# terrarium_board.net
KiCad netlist of a schematic drawn in EAGLE
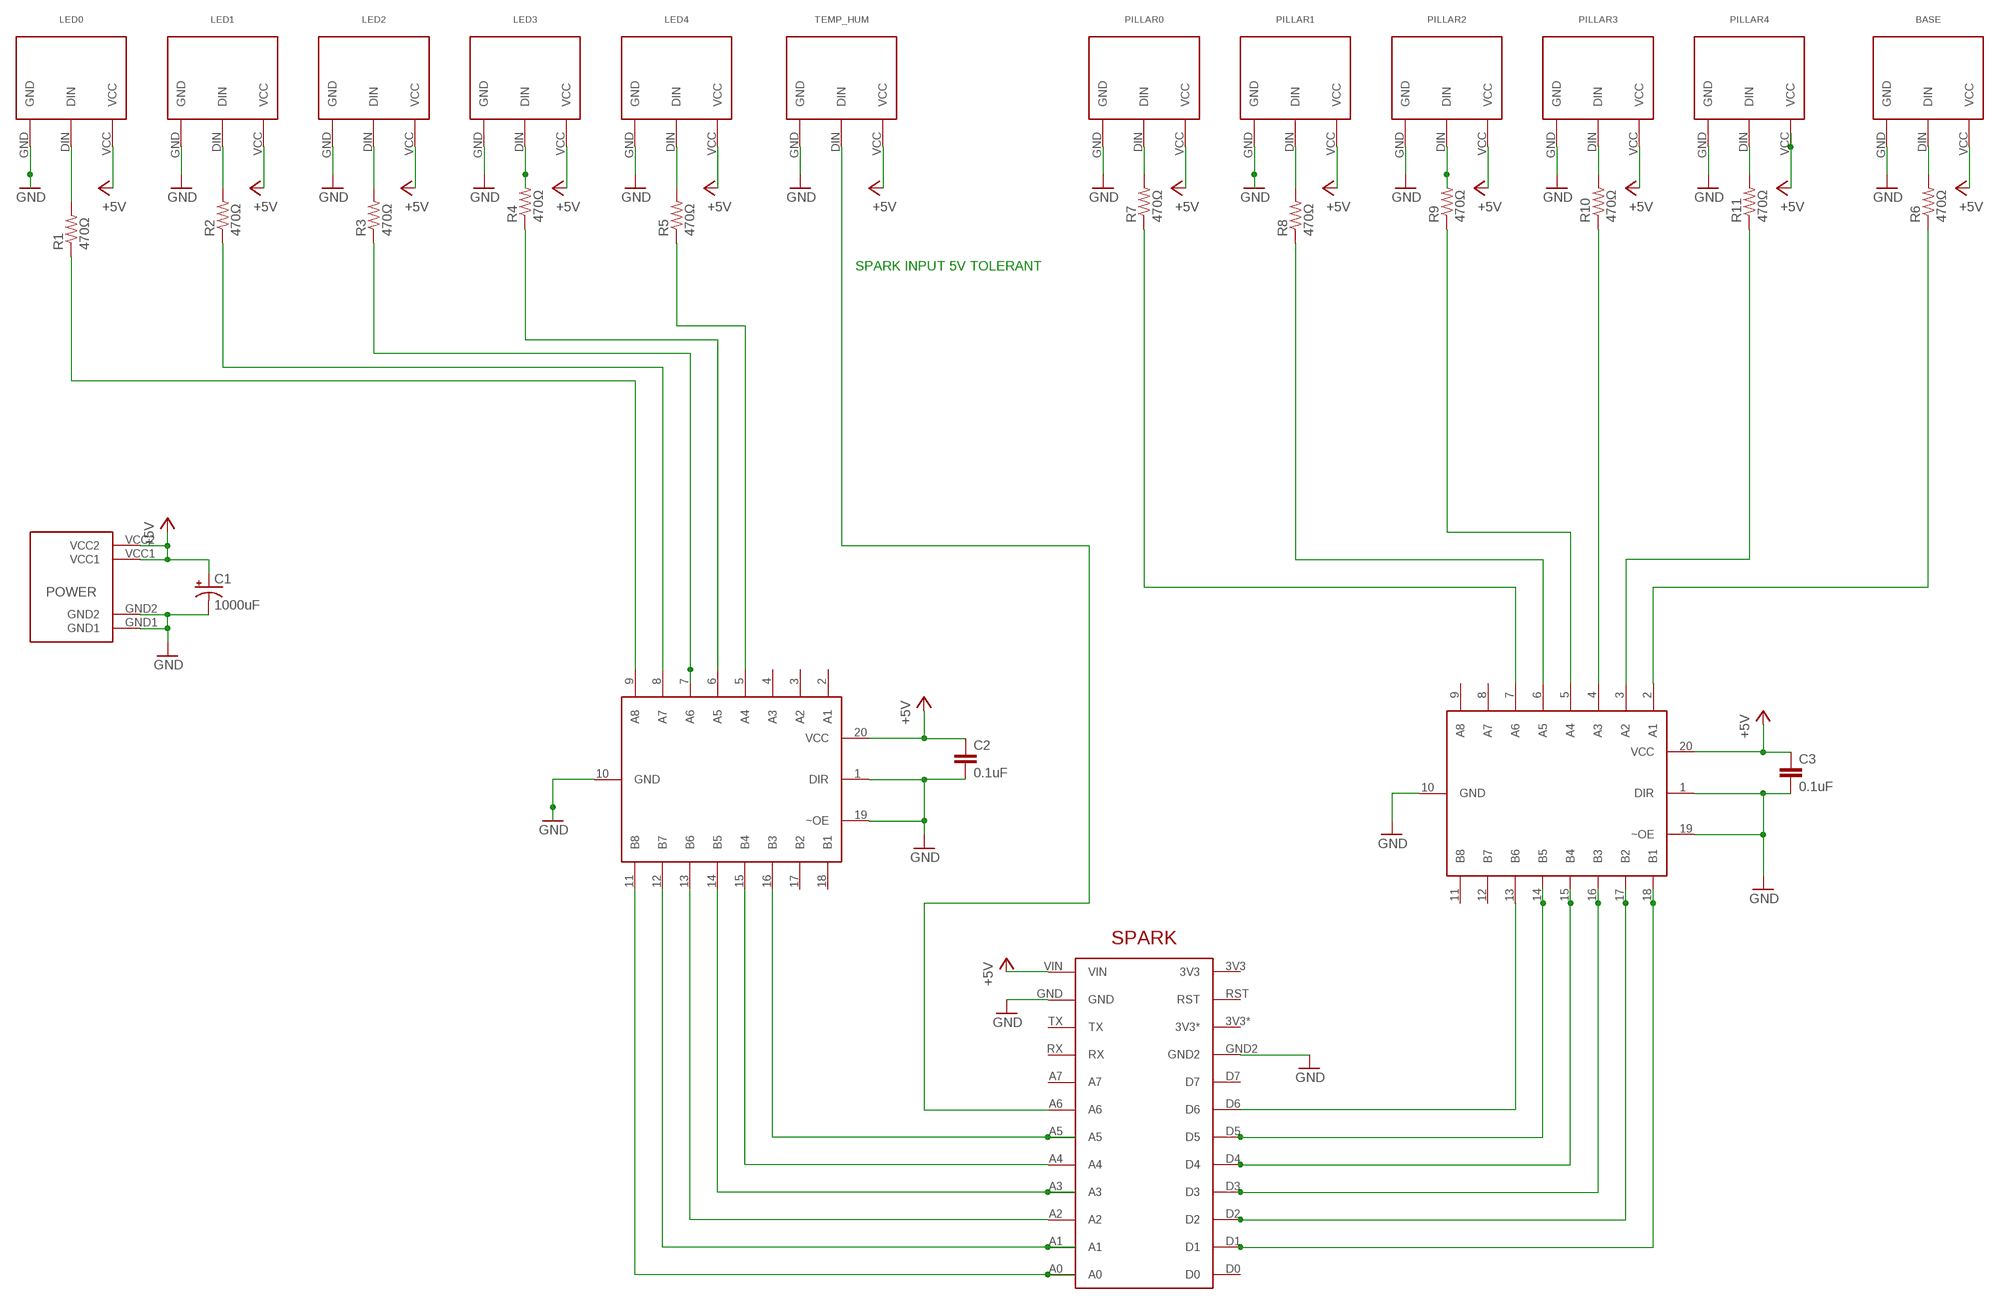
[diagram p0: schematic, sheet 1]

(export (version "E")
  (design (tool "Eeschema 10.0.6"))
  (components
    (comp (ref "BASE")
      (value "MOLEX_3PIN_SMT_43650-310")
      (footprint "eagle-import:MOLEX_3PIN_SMT_43650-310")
      (libsource (lib "eagle-import") (part "MOLEX_3PIN_SMT_43650-310"))
    )
    (comp (ref "C1")
      (value "1000uF")
      (footprint "eagle-import:CPOL-RADIAL-1000UF-25V")
      (libsource (lib "eagle-import") (part "CAP_POLPTH4"))
    )
    (comp (ref "C2")
      (value "0.1uF")
      (footprint "eagle-import:0805")
      (libsource (lib "eagle-import") (part "CAP0805"))
    )
    (comp (ref "C3")
      (value "0.1uF")
      (footprint "eagle-import:0805")
      (libsource (lib "eagle-import") (part "CAP0805"))
    )
    (comp (ref "LED0")
      (value "MOLEX_3PIN_SMT_43650-310")
      (footprint "eagle-import:MOLEX_3PIN_SMT_43650-310")
      (libsource (lib "eagle-import") (part "MOLEX_3PIN_SMT_43650-310"))
    )
    (comp (ref "LED1")
      (value "MOLEX_3PIN_SMT_43650-310")
      (footprint "eagle-import:MOLEX_3PIN_SMT_43650-310")
      (libsource (lib "eagle-import") (part "MOLEX_3PIN_SMT_43650-310"))
    )
    (comp (ref "LED2")
      (value "MOLEX_3PIN_SMT_43650-310")
      (footprint "eagle-import:MOLEX_3PIN_SMT_43650-310")
      (libsource (lib "eagle-import") (part "MOLEX_3PIN_SMT_43650-310"))
    )
    (comp (ref "LED3")
      (value "MOLEX_3PIN_SMT_43650-310")
      (footprint "eagle-import:MOLEX_3PIN_SMT_43650-310")
      (libsource (lib "eagle-import") (part "MOLEX_3PIN_SMT_43650-310"))
    )
    (comp (ref "LED4")
      (value "MOLEX_3PIN_SMT_43650-310")
      (footprint "eagle-import:MOLEX_3PIN_SMT_43650-310")
      (libsource (lib "eagle-import") (part "MOLEX_3PIN_SMT_43650-310"))
    )
    (comp (ref "PILLAR0")
      (value "MOLEX_3PIN_SMT_43650-310")
      (footprint "eagle-import:MOLEX_3PIN_SMT_43650-310")
      (libsource (lib "eagle-import") (part "MOLEX_3PIN_SMT_43650-310"))
    )
    (comp (ref "PILLAR1")
      (value "MOLEX_3PIN_SMT_43650-310")
      (footprint "eagle-import:MOLEX_3PIN_SMT_43650-310")
      (libsource (lib "eagle-import") (part "MOLEX_3PIN_SMT_43650-310"))
    )
    (comp (ref "PILLAR2")
      (value "MOLEX_3PIN_SMT_43650-310")
      (footprint "eagle-import:MOLEX_3PIN_SMT_43650-310")
      (libsource (lib "eagle-import") (part "MOLEX_3PIN_SMT_43650-310"))
    )
    (comp (ref "PILLAR3")
      (value "MOLEX_3PIN_SMT_43650-310")
      (footprint "eagle-import:MOLEX_3PIN_SMT_43650-310")
      (libsource (lib "eagle-import") (part "MOLEX_3PIN_SMT_43650-310"))
    )
    (comp (ref "PILLAR4")
      (value "MOLEX_3PIN_SMT_43650-310")
      (footprint "eagle-import:MOLEX_3PIN_SMT_43650-310")
      (libsource (lib "eagle-import") (part "MOLEX_3PIN_SMT_43650-310"))
    )
    (comp (ref "POWER")
      (value "MOLEX_2PIN_SABRE_POWER")
      (footprint "eagle-import:MOLEX_2PIN_SABRE_POWER")
      (libsource (lib "eagle-import") (part "MOLEX_2PIN_SABRE_POWER"))
    )
    (comp (ref "R1")
      (value "470Ω")
      (footprint "eagle-import:0805")
      (libsource (lib "eagle-import") (part "RESISTOR0805-RES"))
    )
    (comp (ref "R2")
      (value "470Ω")
      (footprint "eagle-import:0805")
      (libsource (lib "eagle-import") (part "RESISTOR0805-RES"))
    )
    (comp (ref "R3")
      (value "470Ω")
      (footprint "eagle-import:0805")
      (libsource (lib "eagle-import") (part "RESISTOR0805-RES"))
    )
    (comp (ref "R4")
      (value "470Ω")
      (footprint "eagle-import:0805")
      (libsource (lib "eagle-import") (part "RESISTOR0805-RES"))
    )
    (comp (ref "R5")
      (value "470Ω")
      (footprint "eagle-import:0805")
      (libsource (lib "eagle-import") (part "RESISTOR0805-RES"))
    )
    (comp (ref "R6")
      (value "470Ω")
      (footprint "eagle-import:0805")
      (libsource (lib "eagle-import") (part "RESISTOR0805-RES"))
    )
    (comp (ref "R7")
      (value "470Ω")
      (footprint "eagle-import:0805")
      (libsource (lib "eagle-import") (part "RESISTOR0805-RES"))
    )
    (comp (ref "R8")
      (value "470Ω")
      (footprint "eagle-import:0805")
      (libsource (lib "eagle-import") (part "RESISTOR0805-RES"))
    )
    (comp (ref "R9")
      (value "470Ω")
      (footprint "eagle-import:0805")
      (libsource (lib "eagle-import") (part "RESISTOR0805-RES"))
    )
    (comp (ref "R10")
      (value "470Ω")
      (footprint "eagle-import:0805")
      (libsource (lib "eagle-import") (part "RESISTOR0805-RES"))
    )
    (comp (ref "R11")
      (value "470Ω")
      (footprint "eagle-import:0805")
      (libsource (lib "eagle-import") (part "RESISTOR0805-RES"))
    )
    (comp (ref "SHIFT1")
      (value "TI_74HCT245DWR")
      (footprint "eagle-import:SOIC-20")
      (libsource (lib "eagle-import") (part "TI_74HCT245DWR"))
    )
    (comp (ref "SHIFT2")
      (value "TI_74HCT245DWR")
      (footprint "eagle-import:SOIC-20")
      (libsource (lib "eagle-import") (part "TI_74HCT245DWR"))
    )
    (comp (ref "SPARK")
      (value "SPARKCORE")
      (footprint "eagle-import:SPARKCORE")
      (libsource (lib "eagle-import") (part "SPARKCORE"))
    )
    (comp (ref "TEMP_HUM")
      (value "MOLEX_3PIN_SMT_43650-310")
      (footprint "eagle-import:MOLEX_3PIN_SMT_43650-310")
      (libsource (lib "eagle-import") (part "MOLEX_3PIN_SMT_43650-310"))
    )
  )
  (nets
    (net (code "1") (name "+5V") (class "Default")
      (node (ref "BASE") (pin "VCC") (pinfunction "VCC_VCC") (pintype "power_in"))
      (node (ref "C1") (pin "1") (pinfunction "+_1") (pintype "passive"))
      (node (ref "C2") (pin "1") (pinfunction "1_1") (pintype "passive"))
      (node (ref "C3") (pin "1") (pinfunction "1_1") (pintype "passive"))
      (node (ref "LED0") (pin "VCC") (pinfunction "VCC_VCC") (pintype "power_in"))
      (node (ref "LED1") (pin "VCC") (pinfunction "VCC_VCC") (pintype "power_in"))
      (node (ref "LED2") (pin "VCC") (pinfunction "VCC_VCC") (pintype "power_in"))
      (node (ref "LED3") (pin "VCC") (pinfunction "VCC_VCC") (pintype "power_in"))
      (node (ref "LED4") (pin "VCC") (pinfunction "VCC_VCC") (pintype "power_in"))
      (node (ref "PILLAR0") (pin "VCC") (pinfunction "VCC_VCC") (pintype "power_in"))
      (node (ref "PILLAR1") (pin "VCC") (pinfunction "VCC_VCC") (pintype "power_in"))
      (node (ref "PILLAR2") (pin "VCC") (pinfunction "VCC_VCC") (pintype "power_in"))
      (node (ref "PILLAR3") (pin "VCC") (pinfunction "VCC_VCC") (pintype "power_in"))
      (node (ref "PILLAR4") (pin "VCC") (pinfunction "VCC_VCC") (pintype "power_in"))
      (node (ref "POWER") (pin "VCC1") (pinfunction "VCC1_VCC1") (pintype "bidirectional"))
      (node (ref "POWER") (pin "VCC2") (pinfunction "VCC2_VCC2") (pintype "power_in"))
      (node (ref "SHIFT1") (pin "20") (pinfunction "VCC_20") (pintype "bidirectional"))
      (node (ref "SHIFT2") (pin "20") (pinfunction "VCC_20") (pintype "bidirectional"))
      (node (ref "SPARK") (pin "VIN") (pinfunction "VIN_VIN") (pintype "power_in"))
      (node (ref "TEMP_HUM") (pin "VCC") (pinfunction "VCC_VCC") (pintype "power_in"))
    )
    (net (code "2") (name "GND") (class "Default")
      (node (ref "BASE") (pin "GND") (pinfunction "GND_GND") (pintype "power_in"))
      (node (ref "C1") (pin "2") (pinfunction "-_2") (pintype "passive"))
      (node (ref "C2") (pin "2") (pinfunction "2_2") (pintype "passive"))
      (node (ref "C3") (pin "2") (pinfunction "2_2") (pintype "passive"))
      (node (ref "LED0") (pin "GND") (pinfunction "GND_GND") (pintype "power_in"))
      (node (ref "LED1") (pin "GND") (pinfunction "GND_GND") (pintype "power_in"))
      (node (ref "LED2") (pin "GND") (pinfunction "GND_GND") (pintype "power_in"))
      (node (ref "LED3") (pin "GND") (pinfunction "GND_GND") (pintype "power_in"))
      (node (ref "LED4") (pin "GND") (pinfunction "GND_GND") (pintype "power_in"))
      (node (ref "PILLAR0") (pin "GND") (pinfunction "GND_GND") (pintype "power_in"))
      (node (ref "PILLAR1") (pin "GND") (pinfunction "GND_GND") (pintype "power_in"))
      (node (ref "PILLAR2") (pin "GND") (pinfunction "GND_GND") (pintype "power_in"))
      (node (ref "PILLAR3") (pin "GND") (pinfunction "GND_GND") (pintype "power_in"))
      (node (ref "PILLAR4") (pin "GND") (pinfunction "GND_GND") (pintype "power_in"))
      (node (ref "POWER") (pin "GND1") (pinfunction "GND1_GND1") (pintype "power_in"))
      (node (ref "POWER") (pin "GND2") (pinfunction "GND2_GND2") (pintype "bidirectional"))
      (node (ref "SHIFT1") (pin "1") (pinfunction "DIR_1") (pintype "bidirectional"))
      (node (ref "SHIFT1") (pin "10") (pinfunction "GND_10") (pintype "bidirectional"))
      (node (ref "SHIFT1") (pin "19") (pinfunction "~{OE}_19") (pintype "bidirectional"))
      (node (ref "SHIFT2") (pin "1") (pinfunction "DIR_1") (pintype "bidirectional"))
      (node (ref "SHIFT2") (pin "10") (pinfunction "GND_10") (pintype "bidirectional"))
      (node (ref "SHIFT2") (pin "19") (pinfunction "~{OE}_19") (pintype "bidirectional"))
      (node (ref "SPARK") (pin "GND") (pinfunction "GND_GND") (pintype "power_in"))
      (node (ref "SPARK") (pin "GND2") (pinfunction "GND2_GND2") (pintype "bidirectional"))
      (node (ref "TEMP_HUM") (pin "GND") (pinfunction "GND_GND") (pintype "power_in"))
    )
    (net (code "3") (name "Net-(BASE-PadDIN)") (class "Default")
      (node (ref "BASE") (pin "DIN") (pinfunction "DIN_DIN") (pintype "bidirectional"))
      (node (ref "R6") (pin "2") (pinfunction "2_2") (pintype "passive"))
    )
    (net (code "4") (name "Net-(LED0-PadDIN)") (class "Default")
      (node (ref "LED0") (pin "DIN") (pinfunction "DIN_DIN") (pintype "bidirectional"))
      (node (ref "R1") (pin "2") (pinfunction "2_2") (pintype "passive"))
    )
    (net (code "5") (name "Net-(LED1-PadDIN)") (class "Default")
      (node (ref "LED1") (pin "DIN") (pinfunction "DIN_DIN") (pintype "bidirectional"))
      (node (ref "R2") (pin "2") (pinfunction "2_2") (pintype "passive"))
    )
    (net (code "6") (name "Net-(LED2-PadDIN)") (class "Default")
      (node (ref "LED2") (pin "DIN") (pinfunction "DIN_DIN") (pintype "bidirectional"))
      (node (ref "R3") (pin "2") (pinfunction "2_2") (pintype "passive"))
    )
    (net (code "7") (name "Net-(LED3-PadDIN)") (class "Default")
      (node (ref "LED3") (pin "DIN") (pinfunction "DIN_DIN") (pintype "bidirectional"))
      (node (ref "R4") (pin "2") (pinfunction "2_2") (pintype "passive"))
    )
    (net (code "8") (name "Net-(LED4-PadDIN)") (class "Default")
      (node (ref "LED4") (pin "DIN") (pinfunction "DIN_DIN") (pintype "bidirectional"))
      (node (ref "R5") (pin "2") (pinfunction "2_2") (pintype "passive"))
    )
    (net (code "9") (name "Net-(PILLAR0-PadDIN)") (class "Default")
      (node (ref "PILLAR0") (pin "DIN") (pinfunction "DIN_DIN") (pintype "bidirectional"))
      (node (ref "R7") (pin "2") (pinfunction "2_2") (pintype "passive"))
    )
    (net (code "10") (name "Net-(PILLAR1-PadDIN)") (class "Default")
      (node (ref "PILLAR1") (pin "DIN") (pinfunction "DIN_DIN") (pintype "bidirectional"))
      (node (ref "R8") (pin "2") (pinfunction "2_2") (pintype "passive"))
    )
    (net (code "11") (name "Net-(PILLAR2-PadDIN)") (class "Default")
      (node (ref "PILLAR2") (pin "DIN") (pinfunction "DIN_DIN") (pintype "bidirectional"))
      (node (ref "R9") (pin "2") (pinfunction "2_2") (pintype "passive"))
    )
    (net (code "12") (name "Net-(PILLAR3-PadDIN)") (class "Default")
      (node (ref "PILLAR3") (pin "DIN") (pinfunction "DIN_DIN") (pintype "bidirectional"))
      (node (ref "R10") (pin "2") (pinfunction "2_2") (pintype "passive"))
    )
    (net (code "13") (name "Net-(PILLAR4-PadDIN)") (class "Default")
      (node (ref "PILLAR4") (pin "DIN") (pinfunction "DIN_DIN") (pintype "bidirectional"))
      (node (ref "R11") (pin "2") (pinfunction "2_2") (pintype "passive"))
    )
    (net (code "14") (name "Net-(SHIFT1-A4)") (class "Default")
      (node (ref "R5") (pin "1") (pinfunction "1_1") (pintype "passive"))
      (node (ref "SHIFT1") (pin "5") (pinfunction "A4_5") (pintype "bidirectional"))
    )
    (net (code "15") (name "Net-(SHIFT1-A5)") (class "Default")
      (node (ref "R4") (pin "1") (pinfunction "1_1") (pintype "passive"))
      (node (ref "SHIFT1") (pin "6") (pinfunction "A5_6") (pintype "bidirectional"))
    )
    (net (code "16") (name "Net-(SHIFT1-A6)") (class "Default")
      (node (ref "R3") (pin "1") (pinfunction "1_1") (pintype "passive"))
      (node (ref "SHIFT1") (pin "7") (pinfunction "A6_7") (pintype "bidirectional"))
    )
    (net (code "17") (name "Net-(SHIFT1-A7)") (class "Default")
      (node (ref "R2") (pin "1") (pinfunction "1_1") (pintype "passive"))
      (node (ref "SHIFT1") (pin "8") (pinfunction "A7_8") (pintype "bidirectional"))
    )
    (net (code "18") (name "Net-(SHIFT1-A8)") (class "Default")
      (node (ref "R1") (pin "1") (pinfunction "1_1") (pintype "passive"))
      (node (ref "SHIFT1") (pin "9") (pinfunction "A8_9") (pintype "bidirectional"))
    )
    (net (code "19") (name "Net-(SHIFT1-B3)") (class "Default")
      (node (ref "SHIFT1") (pin "16") (pinfunction "B3_16") (pintype "bidirectional"))
      (node (ref "SPARK") (pin "A5") (pinfunction "A5_A5") (pintype "bidirectional"))
    )
    (net (code "20") (name "Net-(SHIFT1-B4)") (class "Default")
      (node (ref "SHIFT1") (pin "15") (pinfunction "B4_15") (pintype "bidirectional"))
      (node (ref "SPARK") (pin "A4") (pinfunction "A4_A4") (pintype "bidirectional"))
    )
    (net (code "21") (name "Net-(SHIFT1-B5)") (class "Default")
      (node (ref "SHIFT1") (pin "14") (pinfunction "B5_14") (pintype "bidirectional"))
      (node (ref "SPARK") (pin "A3") (pinfunction "A3_A3") (pintype "bidirectional"))
    )
    (net (code "22") (name "Net-(SHIFT1-B6)") (class "Default")
      (node (ref "SHIFT1") (pin "13") (pinfunction "B6_13") (pintype "bidirectional"))
      (node (ref "SPARK") (pin "A2") (pinfunction "A2_A2") (pintype "bidirectional"))
    )
    (net (code "23") (name "Net-(SHIFT1-B7)") (class "Default")
      (node (ref "SHIFT1") (pin "12") (pinfunction "B7_12") (pintype "bidirectional"))
      (node (ref "SPARK") (pin "A1") (pinfunction "A1_A1") (pintype "bidirectional"))
    )
    (net (code "24") (name "Net-(SHIFT1-B8)") (class "Default")
      (node (ref "SHIFT1") (pin "11") (pinfunction "B8_11") (pintype "bidirectional"))
      (node (ref "SPARK") (pin "A0") (pinfunction "A0_A0") (pintype "bidirectional"))
    )
    (net (code "25") (name "Net-(SHIFT2-A1)") (class "Default")
      (node (ref "R6") (pin "1") (pinfunction "1_1") (pintype "passive"))
      (node (ref "SHIFT2") (pin "2") (pinfunction "A1_2") (pintype "bidirectional"))
    )
    (net (code "26") (name "Net-(SHIFT2-A2)") (class "Default")
      (node (ref "R11") (pin "1") (pinfunction "1_1") (pintype "passive"))
      (node (ref "SHIFT2") (pin "3") (pinfunction "A2_3") (pintype "bidirectional"))
    )
    (net (code "27") (name "Net-(SHIFT2-A3)") (class "Default")
      (node (ref "R10") (pin "1") (pinfunction "1_1") (pintype "passive"))
      (node (ref "SHIFT2") (pin "4") (pinfunction "A3_4") (pintype "bidirectional"))
    )
    (net (code "28") (name "Net-(SHIFT2-A4)") (class "Default")
      (node (ref "R9") (pin "1") (pinfunction "1_1") (pintype "passive"))
      (node (ref "SHIFT2") (pin "5") (pinfunction "A4_5") (pintype "bidirectional"))
    )
    (net (code "29") (name "Net-(SHIFT2-A5)") (class "Default")
      (node (ref "R8") (pin "1") (pinfunction "1_1") (pintype "passive"))
      (node (ref "SHIFT2") (pin "6") (pinfunction "A5_6") (pintype "bidirectional"))
    )
    (net (code "30") (name "Net-(SHIFT2-A6)") (class "Default")
      (node (ref "R7") (pin "1") (pinfunction "1_1") (pintype "passive"))
      (node (ref "SHIFT2") (pin "7") (pinfunction "A6_7") (pintype "bidirectional"))
    )
    (net (code "31") (name "Net-(SHIFT2-B1)") (class "Default")
      (node (ref "SHIFT2") (pin "18") (pinfunction "B1_18") (pintype "bidirectional"))
      (node (ref "SPARK") (pin "D1") (pinfunction "D1_D1") (pintype "bidirectional"))
    )
    (net (code "32") (name "Net-(SHIFT2-B2)") (class "Default")
      (node (ref "SHIFT2") (pin "17") (pinfunction "B2_17") (pintype "bidirectional"))
      (node (ref "SPARK") (pin "D2") (pinfunction "D2_D2") (pintype "bidirectional"))
    )
    (net (code "33") (name "Net-(SHIFT2-B3)") (class "Default")
      (node (ref "SHIFT2") (pin "16") (pinfunction "B3_16") (pintype "bidirectional"))
      (node (ref "SPARK") (pin "D3") (pinfunction "D3_D3") (pintype "bidirectional"))
    )
    (net (code "34") (name "Net-(SHIFT2-B4)") (class "Default")
      (node (ref "SHIFT2") (pin "15") (pinfunction "B4_15") (pintype "bidirectional"))
      (node (ref "SPARK") (pin "D4") (pinfunction "D4_D4") (pintype "bidirectional"))
    )
    (net (code "35") (name "Net-(SHIFT2-B5)") (class "Default")
      (node (ref "SHIFT2") (pin "14") (pinfunction "B5_14") (pintype "bidirectional"))
      (node (ref "SPARK") (pin "D5") (pinfunction "D5_D5") (pintype "bidirectional"))
    )
    (net (code "36") (name "Net-(SHIFT2-B6)") (class "Default")
      (node (ref "SHIFT2") (pin "13") (pinfunction "B6_13") (pintype "bidirectional"))
      (node (ref "SPARK") (pin "D6") (pinfunction "D6_D6") (pintype "bidirectional"))
    )
    (net (code "37") (name "Net-(SPARK-PadA6)") (class "Default")
      (node (ref "SPARK") (pin "A6") (pinfunction "A6_A6") (pintype "bidirectional"))
      (node (ref "TEMP_HUM") (pin "DIN") (pinfunction "DIN_DIN") (pintype "bidirectional"))
    )
    (net (code "38") (name "unconnected-(SHIFT1-A1-Pad2)") (class "Default")
      (node (ref "SHIFT1") (pin "2") (pinfunction "A1_2") (pintype "bidirectional"))
    )
    (net (code "39") (name "unconnected-(SHIFT1-A2-Pad3)") (class "Default")
      (node (ref "SHIFT1") (pin "3") (pinfunction "A2_3") (pintype "bidirectional"))
    )
    (net (code "40") (name "unconnected-(SHIFT1-A3-Pad4)") (class "Default")
      (node (ref "SHIFT1") (pin "4") (pinfunction "A3_4") (pintype "bidirectional"))
    )
    (net (code "41") (name "unconnected-(SHIFT1-B1-Pad18)") (class "Default")
      (node (ref "SHIFT1") (pin "18") (pinfunction "B1_18") (pintype "bidirectional"))
    )
    (net (code "42") (name "unconnected-(SHIFT1-B2-Pad17)") (class "Default")
      (node (ref "SHIFT1") (pin "17") (pinfunction "B2_17") (pintype "bidirectional"))
    )
    (net (code "43") (name "unconnected-(SHIFT2-A7-Pad8)") (class "Default")
      (node (ref "SHIFT2") (pin "8") (pinfunction "A7_8") (pintype "bidirectional"))
    )
    (net (code "44") (name "unconnected-(SHIFT2-A8-Pad9)") (class "Default")
      (node (ref "SHIFT2") (pin "9") (pinfunction "A8_9") (pintype "bidirectional"))
    )
    (net (code "45") (name "unconnected-(SHIFT2-B7-Pad12)") (class "Default")
      (node (ref "SHIFT2") (pin "12") (pinfunction "B7_12") (pintype "bidirectional"))
    )
    (net (code "46") (name "unconnected-(SHIFT2-B8-Pad11)") (class "Default")
      (node (ref "SHIFT2") (pin "11") (pinfunction "B8_11") (pintype "bidirectional"))
    )
    (net (code "47") (name "unconnected-(SPARK-Pad3V3)") (class "Default")
      (node (ref "SPARK") (pin "3V3") (pinfunction "3V3_3V3") (pintype "bidirectional"))
    )
    (net (code "48") (name "unconnected-(SPARK-Pad3V3*)") (class "Default")
      (node (ref "SPARK") (pin "3V3*") (pinfunction "3V3*_3V3*") (pintype "bidirectional"))
    )
    (net (code "49") (name "unconnected-(SPARK-PadA7)") (class "Default")
      (node (ref "SPARK") (pin "A7") (pinfunction "A7_A7") (pintype "bidirectional"))
    )
    (net (code "50") (name "unconnected-(SPARK-PadD0)") (class "Default")
      (node (ref "SPARK") (pin "D0") (pinfunction "D0_D0") (pintype "bidirectional"))
    )
    (net (code "51") (name "unconnected-(SPARK-PadD7)") (class "Default")
      (node (ref "SPARK") (pin "D7") (pinfunction "D7_D7") (pintype "bidirectional"))
    )
    (net (code "52") (name "unconnected-(SPARK-PadRST)") (class "Default")
      (node (ref "SPARK") (pin "RST") (pinfunction "RST_RST") (pintype "bidirectional"))
    )
    (net (code "53") (name "unconnected-(SPARK-PadRX)") (class "Default")
      (node (ref "SPARK") (pin "RX") (pinfunction "RX_RX") (pintype "bidirectional"))
    )
    (net (code "54") (name "unconnected-(SPARK-PadTX)") (class "Default")
      (node (ref "SPARK") (pin "TX") (pinfunction "TX_TX") (pintype "bidirectional"))
    )
  )
)
